# can.net
KiCad netlist of a schematic drawn in Altium Designer
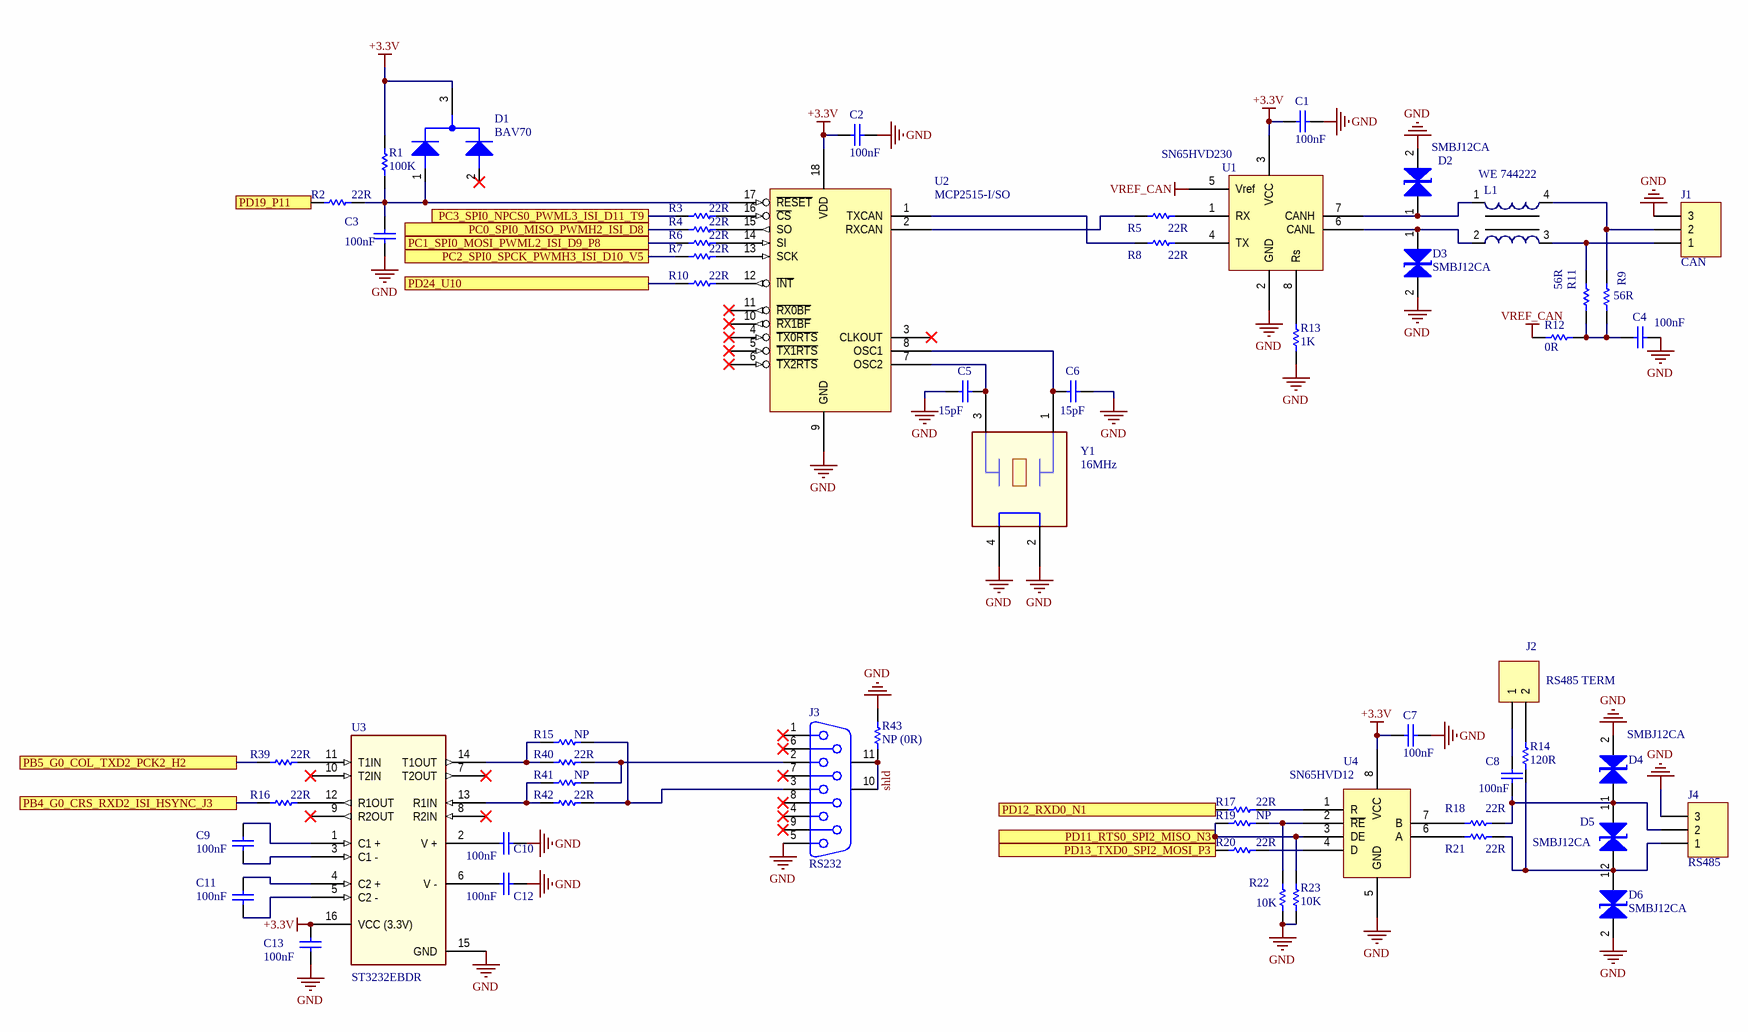
[diagram p0: can.SchDoc]

(export (version "E")
  (design (tool "Eeschema 10.0.6"))
  (components
    (comp (ref "C1")
      (value "100nF")
      (footprint "0603_[1608]")
      (description "Ceramic X7R 50V")
      (fields (field (name "PUBLISHER") "Altium Limited"))
      (libsource (lib "Miscellaneous Devices") (part "Cap"))
    )
    (comp (ref "C2")
      (value "100nF")
      (footprint "0603_[1608]")
      (description "Ceramic X7R 50V")
      (fields (field (name "PUBLISHER") "Altium Limited"))
      (libsource (lib "Miscellaneous Devices") (part "Cap"))
    )
    (comp (ref "C3")
      (value "100nF")
      (footprint "0603_[1608]")
      (description "Ceramic X7R 50V")
      (fields (field (name "PUBLISHER") "Altium Limited"))
      (libsource (lib "Miscellaneous Devices") (part "Cap"))
    )
    (comp (ref "C4")
      (value "100nF")
      (footprint "0603_[1608]")
      (description "Ceramic X7R 50V")
      (fields (field (name "PUBLISHER") "Altium Limited"))
      (libsource (lib "Miscellaneous Devices") (part "Cap"))
    )
    (comp (ref "C5")
      (value "15pF")
      (footprint "0603_[1608]")
      (description "Ceramic 50V NP0/C0G")
      (fields (field (name "PUBLISHER") "Altium Limited"))
      (libsource (lib "Miscellaneous Devices") (part "Cap"))
    )
    (comp (ref "C6")
      (value "15pF")
      (footprint "0603_[1608]")
      (description "Ceramic 50V NP0/C0G")
      (fields (field (name "PUBLISHER") "Altium Limited"))
      (libsource (lib "Miscellaneous Devices") (part "Cap"))
    )
    (comp (ref "C7")
      (value "100nF")
      (footprint "0603_[1608]")
      (description "Ceramic X7R 50V")
      (fields (field (name "PUBLISHER") "Altium Limited"))
      (libsource (lib "Miscellaneous Devices") (part "Cap"))
    )
    (comp (ref "C8")
      (value "100nF")
      (footprint "0603_[1608]")
      (description "Ceramic X7R 50V")
      (fields (field (name "PUBLISHER") "Altium Limited"))
      (libsource (lib "Miscellaneous Devices") (part "Cap"))
    )
    (comp (ref "C9")
      (value "100nF")
      (footprint "0603_[1608]")
      (description "Ceramic X7R 50V")
      (fields (field (name "PUBLISHER") "Altium Limited"))
      (libsource (lib "Miscellaneous Devices") (part "Cap"))
    )
    (comp (ref "C10")
      (value "100nF")
      (footprint "0603_[1608]")
      (description "Ceramic X7R 50V")
      (fields (field (name "PUBLISHER") "Altium Limited"))
      (libsource (lib "Miscellaneous Devices") (part "Cap"))
    )
    (comp (ref "C11")
      (value "100nF")
      (footprint "0603_[1608]")
      (description "Ceramic X7R 50V")
      (fields (field (name "PUBLISHER") "Altium Limited"))
      (libsource (lib "Miscellaneous Devices") (part "Cap"))
    )
    (comp (ref "C12")
      (value "100nF")
      (footprint "0603_[1608]")
      (description "Ceramic X7R 50V")
      (fields (field (name "PUBLISHER") "Altium Limited"))
      (libsource (lib "Miscellaneous Devices") (part "Cap"))
    )
    (comp (ref "C13")
      (value "100nF")
      (footprint "0603_[1608]")
      (description "Ceramic X7R 50V")
      (fields (field (name "PUBLISHER") "Altium Limited"))
      (libsource (lib "Miscellaneous Devices") (part "Cap"))
    )
    (comp (ref "D1")
      (value "BAV70")
      (footprint "SOT-23")
      (description "Diode")
      (libsource (lib "DEVELER_Library") (part "BAV70"))
    )
    (comp (ref "D2")
      (value "SMBJ12CA")
      (footprint "DO214AA_12")
      (description "TVS bidirectional")
      (libsource (lib "DEVELER_Library") (part "TVS bi"))
    )
    (comp (ref "D3")
      (value "SMBJ12CA")
      (footprint "DO214AA_12")
      (description "TVS bidirectional")
      (libsource (lib "DEVELER_Library") (part "TVS bi"))
    )
    (comp (ref "D4")
      (value "SMBJ12CA")
      (footprint "DO214AA_12")
      (description "TVS bidirectional")
      (libsource (lib "DEVELER_Library") (part "TVS bi"))
    )
    (comp (ref "D5")
      (value "SMBJ12CA")
      (footprint "DO214AA_12")
      (description "TVS bidirectional")
      (libsource (lib "DEVELER_Library") (part "TVS bi"))
    )
    (comp (ref "D6")
      (value "SMBJ12CA")
      (footprint "DO214AA_12")
      (description "TVS bidirectional")
      (libsource (lib "DEVELER_Library") (part "TVS bi"))
    )
    (comp (ref "J1")
      (value "CAN")
      (footprint "TBLOCK_1X3_3.5MM_HOR_THD")
      (description "Terminal block Header 3.5mm Horizontal (WE 691322110003)")
      (fields (field (name "PUBLISHER") "Altium Limited"))
      (libsource (lib "Miscellaneous Connectors") (part "Header 3"))
    )
    (comp (ref "J2")
      (value "RS485 TERM")
      (footprint "HEADER_1X2_2.54MM_THD")
      (description "Pin Header, 2.54mm, 1x2, 2pin")
      (fields (field (name "PUBLISHER") "Altium Limited"))
      (libsource (lib "Miscellaneous Connectors") (part "Header 2"))
    )
    (comp (ref "J3")
      (value "RS232")
      (footprint "DSUB1.385-2H9_FEMALE")
      (description "Receptacle Assembly, 9 Position, Right Angle (WE 618009231421)")
      (fields (field (name "PUBLISHER") "Altium Limited"))
      (libsource (lib "Miscellaneous Connectors") (part "D Connector 9"))
    )
    (comp (ref "J4")
      (value "RS485")
      (footprint "TBLOCK_1X3_3.5MM_HOR_THD")
      (description "Terminal block Header 3.5mm Horizontal (WE 691322110003)")
      (fields (field (name "PUBLISHER") "Altium Limited"))
      (libsource (lib "Miscellaneous Connectors") (part "Header 3"))
    )
    (comp (ref "L1")
      (value "WE 744222")
      (footprint "WE-SL2")
      (description "Common Mode line Filter")
      (fields
        (field (name "PARTNO") "744821240")
        (field (name "MANUFACTURER") "Würth Elektronik eiSos GmbH")
        (field (name "CREATED BY") "Christin Zierenner")
      )
      (libsource (lib "DEVELER_Library") (part "WE-CMB XS, 744821240"))
    )
    (comp (ref "R1")
      (value "100K")
      (footprint "0603_[1608]")
      (description "Resistor")
      (libsource (lib "") (part "Res1_1"))
    )
    (comp (ref "R2")
      (value "22R")
      (footprint "0603_[1608]")
      (description "Resistor")
      (fields (field (name "PUBLISHER") "Altium Limited"))
      (libsource (lib "DEVELER_Library") (part "Res1"))
    )
    (comp (ref "R3")
      (value "22R")
      (footprint "0603_[1608]")
      (description "Resistor")
      (libsource (lib "") (part "Res1_1"))
    )
    (comp (ref "R4")
      (value "22R")
      (footprint "0603_[1608]")
      (description "Resistor")
      (libsource (lib "") (part "Res1_1"))
    )
    (comp (ref "R5")
      (value "22R")
      (footprint "0603_[1608]")
      (description "Resistor")
      (libsource (lib "") (part "Res1_1"))
    )
    (comp (ref "R6")
      (value "22R")
      (footprint "0603_[1608]")
      (description "Resistor")
      (libsource (lib "") (part "Res1_1"))
    )
    (comp (ref "R7")
      (value "22R")
      (footprint "0603_[1608]")
      (description "Resistor")
      (libsource (lib "") (part "Res1_1"))
    )
    (comp (ref "R8")
      (value "22R")
      (footprint "0603_[1608]")
      (description "Resistor")
      (libsource (lib "") (part "Res1_1"))
    )
    (comp (ref "R9")
      (value "56R")
      (footprint "0603_[1608]")
      (description "Resistor")
      (libsource (lib "") (part "Res1_1"))
    )
    (comp (ref "R10")
      (value "22R")
      (footprint "0603_[1608]")
      (description "Resistor")
      (libsource (lib "") (part "Res1_1"))
    )
    (comp (ref "R11")
      (value "56R")
      (footprint "0603_[1608]")
      (description "Resistor")
      (libsource (lib "") (part "Res1_1"))
    )
    (comp (ref "R12")
      (value "0R")
      (footprint "0603_[1608]")
      (description "Resistor")
      (libsource (lib "") (part "Res1_1"))
    )
    (comp (ref "R13")
      (value "1K")
      (footprint "0603_[1608]")
      (description "Resistor")
      (libsource (lib "") (part "Res1_1"))
    )
    (comp (ref "R14")
      (value "120R")
      (footprint "0603_[1608]")
      (description "Resistor")
      (libsource (lib "") (part "Res1_1"))
    )
    (comp (ref "R15")
      (value "NP")
      (footprint "0603_[1608]")
      (description "Resistor")
      (libsource (lib "") (part "Res1_1"))
    )
    (comp (ref "R16")
      (value "22R")
      (footprint "0603_[1608]")
      (description "Resistor")
      (libsource (lib "") (part "Res1_1"))
    )
    (comp (ref "R17")
      (value "22R")
      (footprint "0603_[1608]")
      (description "Resistor")
      (fields (field (name "PUBLISHER") "Altium Limited"))
      (libsource (lib "DEVELER_Library") (part "Res1"))
    )
    (comp (ref "R18")
      (value "22R")
      (footprint "0603_[1608]")
      (description "Resistor")
      (libsource (lib "") (part "Res1_1"))
    )
    (comp (ref "R19")
      (value "NP")
      (footprint "0603_[1608]")
      (description "Resistor")
      (libsource (lib "") (part "Res1_1"))
    )
    (comp (ref "R20")
      (value "22R")
      (footprint "0603_[1608]")
      (description "Resistor")
      (fields (field (name "PUBLISHER") "Altium Limited"))
      (libsource (lib "DEVELER_Library") (part "Res1"))
    )
    (comp (ref "R21")
      (value "22R")
      (footprint "0603_[1608]")
      (description "Resistor")
      (libsource (lib "") (part "Res1_1"))
    )
    (comp (ref "R22")
      (value "10K")
      (footprint "0603_[1608]")
      (description "Resistor")
      (libsource (lib "") (part "Res1_1"))
    )
    (comp (ref "R23")
      (value "10K")
      (footprint "0603_[1608]")
      (description "Resistor")
      (libsource (lib "") (part "Res1_1"))
    )
    (comp (ref "R39")
      (value "22R")
      (footprint "0603_[1608]")
      (description "Resistor")
      (libsource (lib "") (part "Res1_1"))
    )
    (comp (ref "R40")
      (value "22R")
      (footprint "0603_[1608]")
      (description "Resistor")
      (libsource (lib "") (part "Res1_1"))
    )
    (comp (ref "R41")
      (value "NP")
      (footprint "0603_[1608]")
      (description "Resistor")
      (libsource (lib "") (part "Res1_1"))
    )
    (comp (ref "R42")
      (value "22R")
      (footprint "0603_[1608]")
      (description "Resistor")
      (libsource (lib "") (part "Res1_1"))
    )
    (comp (ref "R43")
      (value "NP (0R)")
      (footprint "0603_[1608]")
      (description "Resistor")
      (fields (field (name "PUBLISHER") "Altium Limited"))
      (libsource (lib "DEVELER_Library") (part "Res1"))
    )
    (comp (ref "U1")
      (value "SN65HVD230")
      (footprint "SOIC8")
      (description "3.3V CAN bus transceiver (SN65HVD231; SN65HVD232)")
      (libsource (lib "DEVELER_Library") (part "SN65HVD230"))
    )
    (comp (ref "U2")
      (value "MCP2515-I/SO")
      (footprint "SOIC18")
      (description "Stand-Alone CAN controller with SPI interface")
      (libsource (lib "DEVELER_Library") (part "MCP2515"))
    )
    (comp (ref "U3")
      (value "ST3232EBDR")
      (footprint "SOIC16")
      (description "3 to 5.5 V, low power, up to 400 kbps RS-232 driver")
      (fields (field (name "PART NUMBER") "STm ST3232CDR"))
      (libsource (lib "DEVELER_Library") (part "ST3232CDR"))
    )
    (comp (ref "U4")
      (value "SN65HVD12")
      (footprint "SOIC8")
      (description "3.3V to RS485 interface")
      (libsource (lib "DEVELER_Library") (part "SN65HVD12"))
    )
    (comp (ref "Y1")
      (value "16MHz")
      (footprint "CRYSTAL_3.2X2.5MM_4P_SMD")
      (description "Crystal")
      (libsource (lib "DEVELER_Library") (part "CRYSTAL-4p"))
    )
  )
  (nets
    (net (code "1") (name "+3.3V") (class "Default")
      (node (ref "C1") (pin "2") (pinfunction "2_2") (pintype "passive"))
      (node (ref "C13") (pin "2") (pinfunction "2_2") (pintype "passive"))
      (node (ref "C2") (pin "2") (pinfunction "2_2") (pintype "passive"))
      (node (ref "C7") (pin "2") (pinfunction "2_2") (pintype "passive"))
      (node (ref "D1") (pin "3") (pinfunction "3_3") (pintype "passive"))
      (node (ref "R1") (pin "1") (pinfunction "1_1") (pintype "passive"))
      (node (ref "U1") (pin "3") (pinfunction "VCC_3") (pintype "power_in"))
      (node (ref "U2") (pin "18") (pinfunction "VDD_18") (pintype "power_in"))
      (node (ref "U3") (pin "16") (pinfunction "VCC_(3.3V)_16") (pintype "power_in"))
      (node (ref "U4") (pin "8") (pinfunction "VCC_8") (pintype "power_in"))
    )
    (net (code "2") (name "/PB4_G0_CRS_RXD2_ISI_HSYNC_J3") (class "Default")
      (node (ref "R16") (pin "1") (pinfunction "1_1") (pintype "passive"))
    )
    (net (code "3") (name "/PB5_G0_COL_TXD2_PCK2_H2") (class "Default")
      (node (ref "R39") (pin "1") (pinfunction "1_1") (pintype "passive"))
    )
    (net (code "4") (name "/PC0_SPI0_MISO_PWMH2_ISI_D8") (class "Default")
      (node (ref "R4") (pin "1") (pinfunction "1_1") (pintype "passive"))
    )
    (net (code "5") (name "/PC1_SPI0_MOSI_PWML2_ISI_D9_P8") (class "Default")
      (node (ref "R6") (pin "1") (pinfunction "1_1") (pintype "passive"))
    )
    (net (code "6") (name "/PC2_SPI0_SPCK_PWMH3_ISI_D10_V5") (class "Default")
      (node (ref "R7") (pin "1") (pinfunction "1_1") (pintype "passive"))
    )
    (net (code "7") (name "/PC3_SPI0_NPCS0_PWML3_ISI_D11_T9") (class "Default")
      (node (ref "R3") (pin "1") (pinfunction "1_1") (pintype "passive"))
    )
    (net (code "8") (name "/PD11_RTS0_SPI2_MISO_N3") (class "Default")
      (node (ref "R19") (pin "2") (pinfunction "2_2") (pintype "passive"))
      (node (ref "R23") (pin "2") (pinfunction "2_2") (pintype "passive"))
      (node (ref "U4") (pin "3") (pinfunction "DE_3") (pintype "passive"))
    )
    (net (code "9") (name "/PD12_RXD0_N1") (class "Default")
      (node (ref "R17") (pin "2") (pinfunction "2_2") (pintype "passive"))
    )
    (net (code "10") (name "/PD13_TXD0_SPI2_MOSI_P3") (class "Default")
      (node (ref "R20") (pin "2") (pinfunction "2_2") (pintype "passive"))
    )
    (net (code "11") (name "/PD19_P11") (class "Default")
      (node (ref "R2") (pin "2") (pinfunction "2_2") (pintype "passive"))
    )
    (net (code "12") (name "/PD24_U10") (class "Default")
      (node (ref "R10") (pin "1") (pinfunction "1_1") (pintype "passive"))
    )
    (net (code "13") (name "/shld") (class "Default")
      (node (ref "J3") (pin "10") (pinfunction "MH1_10") (pintype "passive"))
      (node (ref "J3") (pin "11") (pinfunction "MH2_11") (pintype "passive"))
      (node (ref "R43") (pin "2") (pinfunction "2_2") (pintype "passive"))
    )
    (net (code "14") (name "GND") (class "Default")
      (node (ref "C1") (pin "1") (pinfunction "1_1") (pintype "passive"))
      (node (ref "C10") (pin "1") (pinfunction "1_1") (pintype "passive"))
      (node (ref "C12") (pin "1") (pinfunction "1_1") (pintype "passive"))
      (node (ref "C13") (pin "1") (pinfunction "1_1") (pintype "passive"))
      (node (ref "C2") (pin "1") (pinfunction "1_1") (pintype "passive"))
      (node (ref "C3") (pin "2") (pinfunction "2_2") (pintype "passive"))
      (node (ref "C4") (pin "1") (pinfunction "1_1") (pintype "passive"))
      (node (ref "C5") (pin "2") (pinfunction "2_2") (pintype "passive"))
      (node (ref "C6") (pin "1") (pinfunction "1_1") (pintype "passive"))
      (node (ref "C7") (pin "1") (pinfunction "1_1") (pintype "passive"))
      (node (ref "D2") (pin "2") (pinfunction "2_2") (pintype "passive"))
      (node (ref "D3") (pin "2") (pinfunction "2_2") (pintype "passive"))
      (node (ref "D4") (pin "2") (pinfunction "2_2") (pintype "passive"))
      (node (ref "D6") (pin "2") (pinfunction "2_2") (pintype "passive"))
      (node (ref "J1") (pin "3") (pinfunction "3_3") (pintype "passive"))
      (node (ref "J3") (pin "5") (pinfunction "5_5") (pintype "passive"))
      (node (ref "J4") (pin "3") (pinfunction "3_3") (pintype "passive"))
      (node (ref "R13") (pin "1") (pinfunction "1_1") (pintype "passive"))
      (node (ref "R22") (pin "1") (pinfunction "1_1") (pintype "passive"))
      (node (ref "R23") (pin "1") (pinfunction "1_1") (pintype "passive"))
      (node (ref "R43") (pin "1") (pinfunction "1_1") (pintype "passive"))
      (node (ref "U1") (pin "2") (pinfunction "GND_2") (pintype "power_in"))
      (node (ref "U2") (pin "9") (pinfunction "GND_9") (pintype "power_in"))
      (node (ref "U3") (pin "15") (pinfunction "GND_15") (pintype "power_in"))
      (node (ref "U4") (pin "5") (pinfunction "GND_5") (pintype "power_in"))
      (node (ref "Y1") (pin "2") (pinfunction "2_2") (pintype "passive"))
      (node (ref "Y1") (pin "4") (pinfunction "4_4") (pintype "passive"))
    )
    (net (code "15") (name "Net-(C4-Pad2)") (class "Default")
      (node (ref "C4") (pin "2") (pinfunction "2_2") (pintype "passive"))
      (node (ref "R11") (pin "2") (pinfunction "2_2") (pintype "passive"))
      (node (ref "R12") (pin "2") (pinfunction "2_2") (pintype "passive"))
      (node (ref "R9") (pin "2") (pinfunction "2_2") (pintype "passive"))
    )
    (net (code "16") (name "Net-(C8-Pad1)") (class "Default")
      (node (ref "C8") (pin "1") (pinfunction "1_1") (pintype "passive"))
      (node (ref "J2") (pin "1") (pinfunction "1_1") (pintype "passive"))
    )
    (net (code "17") (name "Net-(C8-Pad2)") (class "Default")
      (node (ref "C8") (pin "2") (pinfunction "2_2") (pintype "passive"))
      (node (ref "D4") (pin "1") (pinfunction "1_1") (pintype "passive"))
      (node (ref "D5") (pin "1") (pinfunction "1_1") (pintype "passive"))
      (node (ref "J4") (pin "2") (pinfunction "2_2") (pintype "passive"))
      (node (ref "R18") (pin "2") (pinfunction "2_2") (pintype "passive"))
    )
    (net (code "18") (name "Net-(D5-Pad2)") (class "Default")
      (node (ref "D5") (pin "2") (pinfunction "2_2") (pintype "passive"))
      (node (ref "D6") (pin "1") (pinfunction "1_1") (pintype "passive"))
      (node (ref "J4") (pin "1") (pinfunction "1_1") (pintype "passive"))
      (node (ref "R14") (pin "2") (pinfunction "2_2") (pintype "passive"))
      (node (ref "R21") (pin "2") (pinfunction "2_2") (pintype "passive"))
    )
    (net (code "19") (name "Net-(J1-Pad1)") (class "Default")
      (node (ref "J1") (pin "1") (pinfunction "1_1") (pintype "passive"))
      (node (ref "L1") (pin "3") (pinfunction "3_3") (pintype "passive"))
      (node (ref "R11") (pin "1") (pinfunction "1_1") (pintype "passive"))
    )
    (net (code "20") (name "Net-(J1-Pad2)") (class "Default")
      (node (ref "J1") (pin "2") (pinfunction "2_2") (pintype "passive"))
      (node (ref "L1") (pin "4") (pinfunction "4_4") (pintype "passive"))
      (node (ref "R9") (pin "1") (pinfunction "1_1") (pintype "passive"))
    )
    (net (code "21") (name "Net-(J2-Pad2)") (class "Default")
      (node (ref "J2") (pin "2") (pinfunction "2_2") (pintype "passive"))
      (node (ref "R14") (pin "1") (pinfunction "1_1") (pintype "passive"))
    )
    (net (code "22") (name "Net-(J3-Pad2)") (class "Default")
      (node (ref "J3") (pin "2") (pinfunction "2_2") (pintype "passive"))
      (node (ref "R40") (pin "2") (pinfunction "2_2") (pintype "passive"))
      (node (ref "R41") (pin "2") (pinfunction "2_2") (pintype "passive"))
    )
    (net (code "23") (name "Net-(J3-Pad3)") (class "Default")
      (node (ref "J3") (pin "3") (pinfunction "3_3") (pintype "passive"))
      (node (ref "R15") (pin "2") (pinfunction "2_2") (pintype "passive"))
      (node (ref "R42") (pin "2") (pinfunction "2_2") (pintype "passive"))
    )
    (net (code "24") (name "Net-(U1-CANH)") (class "Default")
      (node (ref "D2") (pin "1") (pinfunction "1_1") (pintype "passive"))
      (node (ref "L1") (pin "1") (pinfunction "1_1") (pintype "passive"))
      (node (ref "U1") (pin "7") (pinfunction "CANH_7") (pintype "passive"))
    )
    (net (code "25") (name "Net-(U1-CANL)") (class "Default")
      (node (ref "D3") (pin "1") (pinfunction "1_1") (pintype "passive"))
      (node (ref "L1") (pin "2") (pinfunction "2_2") (pintype "passive"))
      (node (ref "U1") (pin "6") (pinfunction "CANL_6") (pintype "passive"))
    )
    (net (code "26") (name "Net-(U1-RX)") (class "Default")
      (node (ref "R5") (pin "2") (pinfunction "2_2") (pintype "passive"))
      (node (ref "U1") (pin "1") (pinfunction "RX_1") (pintype "passive"))
    )
    (net (code "27") (name "Net-(U1-Rs)") (class "Default")
      (node (ref "R13") (pin "2") (pinfunction "2_2") (pintype "passive"))
      (node (ref "U1") (pin "8") (pinfunction "Rs_8") (pintype "passive"))
    )
    (net (code "28") (name "Net-(U1-TX)") (class "Default")
      (node (ref "R8") (pin "2") (pinfunction "2_2") (pintype "passive"))
      (node (ref "U1") (pin "4") (pinfunction "TX_4") (pintype "passive"))
    )
    (net (code "29") (name "Net-(U2-OSC1)") (class "Default")
      (node (ref "C6") (pin "2") (pinfunction "2_2") (pintype "passive"))
      (node (ref "U2") (pin "8") (pinfunction "OSC1_8") (pintype "passive"))
      (node (ref "Y1") (pin "1") (pinfunction "1_1") (pintype "passive"))
    )
    (net (code "30") (name "Net-(U2-OSC2)") (class "Default")
      (node (ref "C5") (pin "1") (pinfunction "1_1") (pintype "passive"))
      (node (ref "U2") (pin "7") (pinfunction "OSC2_7") (pintype "passive"))
      (node (ref "Y1") (pin "3") (pinfunction "3_3") (pintype "passive"))
    )
    (net (code "31") (name "Net-(U2-RXCAN)") (class "Default")
      (node (ref "R5") (pin "1") (pinfunction "1_1") (pintype "passive"))
      (node (ref "U2") (pin "2") (pinfunction "RXCAN_2") (pintype "passive"))
    )
    (net (code "32") (name "Net-(U2-SCK)") (class "Default")
      (node (ref "R7") (pin "2") (pinfunction "2_2") (pintype "passive"))
      (node (ref "U2") (pin "13") (pinfunction "SCK_13") (pintype "input"))
    )
    (net (code "33") (name "Net-(U2-SI)") (class "Default")
      (node (ref "R6") (pin "2") (pinfunction "2_2") (pintype "passive"))
      (node (ref "U2") (pin "14") (pinfunction "SI_14") (pintype "input"))
    )
    (net (code "34") (name "Net-(U2-SO)") (class "Default")
      (node (ref "R4") (pin "2") (pinfunction "2_2") (pintype "passive"))
      (node (ref "U2") (pin "15") (pinfunction "SO_15") (pintype "output"))
    )
    (net (code "35") (name "Net-(U2-TXCAN)") (class "Default")
      (node (ref "R8") (pin "1") (pinfunction "1_1") (pintype "passive"))
      (node (ref "U2") (pin "1") (pinfunction "TXCAN_1") (pintype "passive"))
    )
    (net (code "36") (name "Net-(U2-~{CS})") (class "Default")
      (node (ref "R3") (pin "2") (pinfunction "2_2") (pintype "passive"))
      (node (ref "U2") (pin "16") (pinfunction "~{CS}_16") (pintype "input"))
    )
    (net (code "37") (name "Net-(U2-~{INT})") (class "Default")
      (node (ref "R10") (pin "2") (pinfunction "2_2") (pintype "passive"))
      (node (ref "U2") (pin "12") (pinfunction "~{INT}_12") (pintype "output"))
    )
    (net (code "38") (name "Net-(U2-~{RESET})") (class "Default")
      (node (ref "C3") (pin "1") (pinfunction "1_1") (pintype "passive"))
      (node (ref "D1") (pin "1") (pinfunction "1_1") (pintype "passive"))
      (node (ref "R1") (pin "2") (pinfunction "2_2") (pintype "passive"))
      (node (ref "R2") (pin "1") (pinfunction "1_1") (pintype "passive"))
      (node (ref "U2") (pin "17") (pinfunction "~{RESET}_17") (pintype "input"))
    )
    (net (code "39") (name "Net-(U3-C1_+)") (class "Default")
      (node (ref "C9") (pin "1") (pinfunction "1_1") (pintype "passive"))
      (node (ref "U3") (pin "1") (pinfunction "C1_+_1") (pintype "input"))
    )
    (net (code "40") (name "Net-(U3-C1_-)") (class "Default")
      (node (ref "C9") (pin "2") (pinfunction "2_2") (pintype "passive"))
      (node (ref "U3") (pin "3") (pinfunction "C1_-_3") (pintype "input"))
    )
    (net (code "41") (name "Net-(U3-C2_+)") (class "Default")
      (node (ref "C11") (pin "2") (pinfunction "2_2") (pintype "passive"))
      (node (ref "U3") (pin "4") (pinfunction "C2_+_4") (pintype "input"))
    )
    (net (code "42") (name "Net-(U3-C2_-)") (class "Default")
      (node (ref "C11") (pin "1") (pinfunction "1_1") (pintype "passive"))
      (node (ref "U3") (pin "5") (pinfunction "C2_-_5") (pintype "input"))
    )
    (net (code "43") (name "Net-(U3-R1IN)") (class "Default")
      (node (ref "R41") (pin "1") (pinfunction "1_1") (pintype "passive"))
      (node (ref "R42") (pin "1") (pinfunction "1_1") (pintype "passive"))
      (node (ref "U3") (pin "13") (pinfunction "R1IN_13") (pintype "input"))
    )
    (net (code "44") (name "Net-(U3-R1OUT)") (class "Default")
      (node (ref "R16") (pin "2") (pinfunction "2_2") (pintype "passive"))
      (node (ref "U3") (pin "12") (pinfunction "R1OUT_12") (pintype "output"))
    )
    (net (code "45") (name "Net-(U3-T1IN)") (class "Default")
      (node (ref "R39") (pin "2") (pinfunction "2_2") (pintype "passive"))
      (node (ref "U3") (pin "11") (pinfunction "T1IN_11") (pintype "input"))
    )
    (net (code "46") (name "Net-(U3-T1OUT)") (class "Default")
      (node (ref "R15") (pin "1") (pinfunction "1_1") (pintype "passive"))
      (node (ref "R40") (pin "1") (pinfunction "1_1") (pintype "passive"))
      (node (ref "U3") (pin "14") (pinfunction "T1OUT_14") (pintype "output"))
    )
    (net (code "47") (name "Net-(U3-V_+)") (class "Default")
      (node (ref "C10") (pin "2") (pinfunction "2_2") (pintype "passive"))
      (node (ref "U3") (pin "2") (pinfunction "V_+_2") (pintype "power_in"))
    )
    (net (code "48") (name "Net-(U3-V_-)") (class "Default")
      (node (ref "C12") (pin "2") (pinfunction "2_2") (pintype "passive"))
      (node (ref "U3") (pin "6") (pinfunction "V_-_6") (pintype "power_in"))
    )
    (net (code "49") (name "Net-(U4-A)") (class "Default")
      (node (ref "R21") (pin "1") (pinfunction "1_1") (pintype "passive"))
      (node (ref "U4") (pin "6") (pinfunction "A_6") (pintype "passive"))
    )
    (net (code "50") (name "Net-(U4-B)") (class "Default")
      (node (ref "R18") (pin "1") (pinfunction "1_1") (pintype "passive"))
      (node (ref "U4") (pin "7") (pinfunction "B_7") (pintype "passive"))
    )
    (net (code "51") (name "Net-(U4-D)") (class "Default")
      (node (ref "R20") (pin "1") (pinfunction "1_1") (pintype "passive"))
      (node (ref "U4") (pin "4") (pinfunction "D_4") (pintype "passive"))
    )
    (net (code "52") (name "Net-(U4-R)") (class "Default")
      (node (ref "R17") (pin "1") (pinfunction "1_1") (pintype "passive"))
      (node (ref "U4") (pin "1") (pinfunction "R_1") (pintype "passive"))
    )
    (net (code "53") (name "Net-(U4-~{RE})") (class "Default")
      (node (ref "R19") (pin "1") (pinfunction "1_1") (pintype "passive"))
      (node (ref "R22") (pin "2") (pinfunction "2_2") (pintype "passive"))
      (node (ref "U4") (pin "2") (pinfunction "~{RE}_2") (pintype "passive"))
    )
    (net (code "54") (name "VREF_CAN") (class "Default")
      (node (ref "R12") (pin "1") (pinfunction "1_1") (pintype "passive"))
      (node (ref "U1") (pin "5") (pinfunction "Vref_5") (pintype "passive"))
    )
    (net (code "55") (name "unconnected-(D1-Pad2)") (class "Default")
      (node (ref "D1") (pin "2") (pinfunction "2_2") (pintype "passive+no_connect"))
    )
    (net (code "56") (name "unconnected-(J3-Pad1)") (class "Default")
      (node (ref "J3") (pin "1") (pinfunction "1_1") (pintype "passive+no_connect"))
    )
    (net (code "57") (name "unconnected-(J3-Pad4)") (class "Default")
      (node (ref "J3") (pin "4") (pinfunction "4_4") (pintype "passive+no_connect"))
    )
    (net (code "58") (name "unconnected-(J3-Pad6)") (class "Default")
      (node (ref "J3") (pin "6") (pinfunction "6_6") (pintype "passive+no_connect"))
    )
    (net (code "59") (name "unconnected-(J3-Pad7)") (class "Default")
      (node (ref "J3") (pin "7") (pinfunction "7_7") (pintype "passive+no_connect"))
    )
    (net (code "60") (name "unconnected-(J3-Pad8)") (class "Default")
      (node (ref "J3") (pin "8") (pinfunction "8_8") (pintype "passive+no_connect"))
    )
    (net (code "61") (name "unconnected-(J3-Pad9)") (class "Default")
      (node (ref "J3") (pin "9") (pinfunction "9_9") (pintype "passive+no_connect"))
    )
    (net (code "62") (name "unconnected-(U2-CLKOUT-Pad3)") (class "Default")
      (node (ref "U2") (pin "3") (pinfunction "CLKOUT_3") (pintype "passive+no_connect"))
    )
    (net (code "63") (name "unconnected-(U2-~{RX0BF}-Pad11)") (class "Default")
      (node (ref "U2") (pin "11") (pinfunction "~{RX0BF}_11") (pintype "output+no_connect"))
    )
    (net (code "64") (name "unconnected-(U2-~{RX1BF}-Pad10)") (class "Default")
      (node (ref "U2") (pin "10") (pinfunction "~{RX1BF}_10") (pintype "output+no_connect"))
    )
    (net (code "65") (name "unconnected-(U2-~{TX0RTS}-Pad4)") (class "Default")
      (node (ref "U2") (pin "4") (pinfunction "~{TX0RTS}_4") (pintype "input+no_connect"))
    )
    (net (code "66") (name "unconnected-(U2-~{TX1RTS}-Pad5)") (class "Default")
      (node (ref "U2") (pin "5") (pinfunction "~{TX1RTS}_5") (pintype "input+no_connect"))
    )
    (net (code "67") (name "unconnected-(U2-~{TX2RTS}-Pad6)") (class "Default")
      (node (ref "U2") (pin "6") (pinfunction "~{TX2RTS}_6") (pintype "input+no_connect"))
    )
    (net (code "68") (name "unconnected-(U3-R2IN-Pad8)") (class "Default")
      (node (ref "U3") (pin "8") (pinfunction "R2IN_8") (pintype "input+no_connect"))
    )
    (net (code "69") (name "unconnected-(U3-R2OUT-Pad9)") (class "Default")
      (node (ref "U3") (pin "9") (pinfunction "R2OUT_9") (pintype "output+no_connect"))
    )
    (net (code "70") (name "unconnected-(U3-T2IN-Pad10)") (class "Default")
      (node (ref "U3") (pin "10") (pinfunction "T2IN_10") (pintype "input+no_connect"))
    )
    (net (code "71") (name "unconnected-(U3-T2OUT-Pad7)") (class "Default")
      (node (ref "U3") (pin "7") (pinfunction "T2OUT_7") (pintype "output+no_connect"))
    )
  )
)
